# BTPlayer.net
KiCad netlist of a schematic drawn in EasyEDA
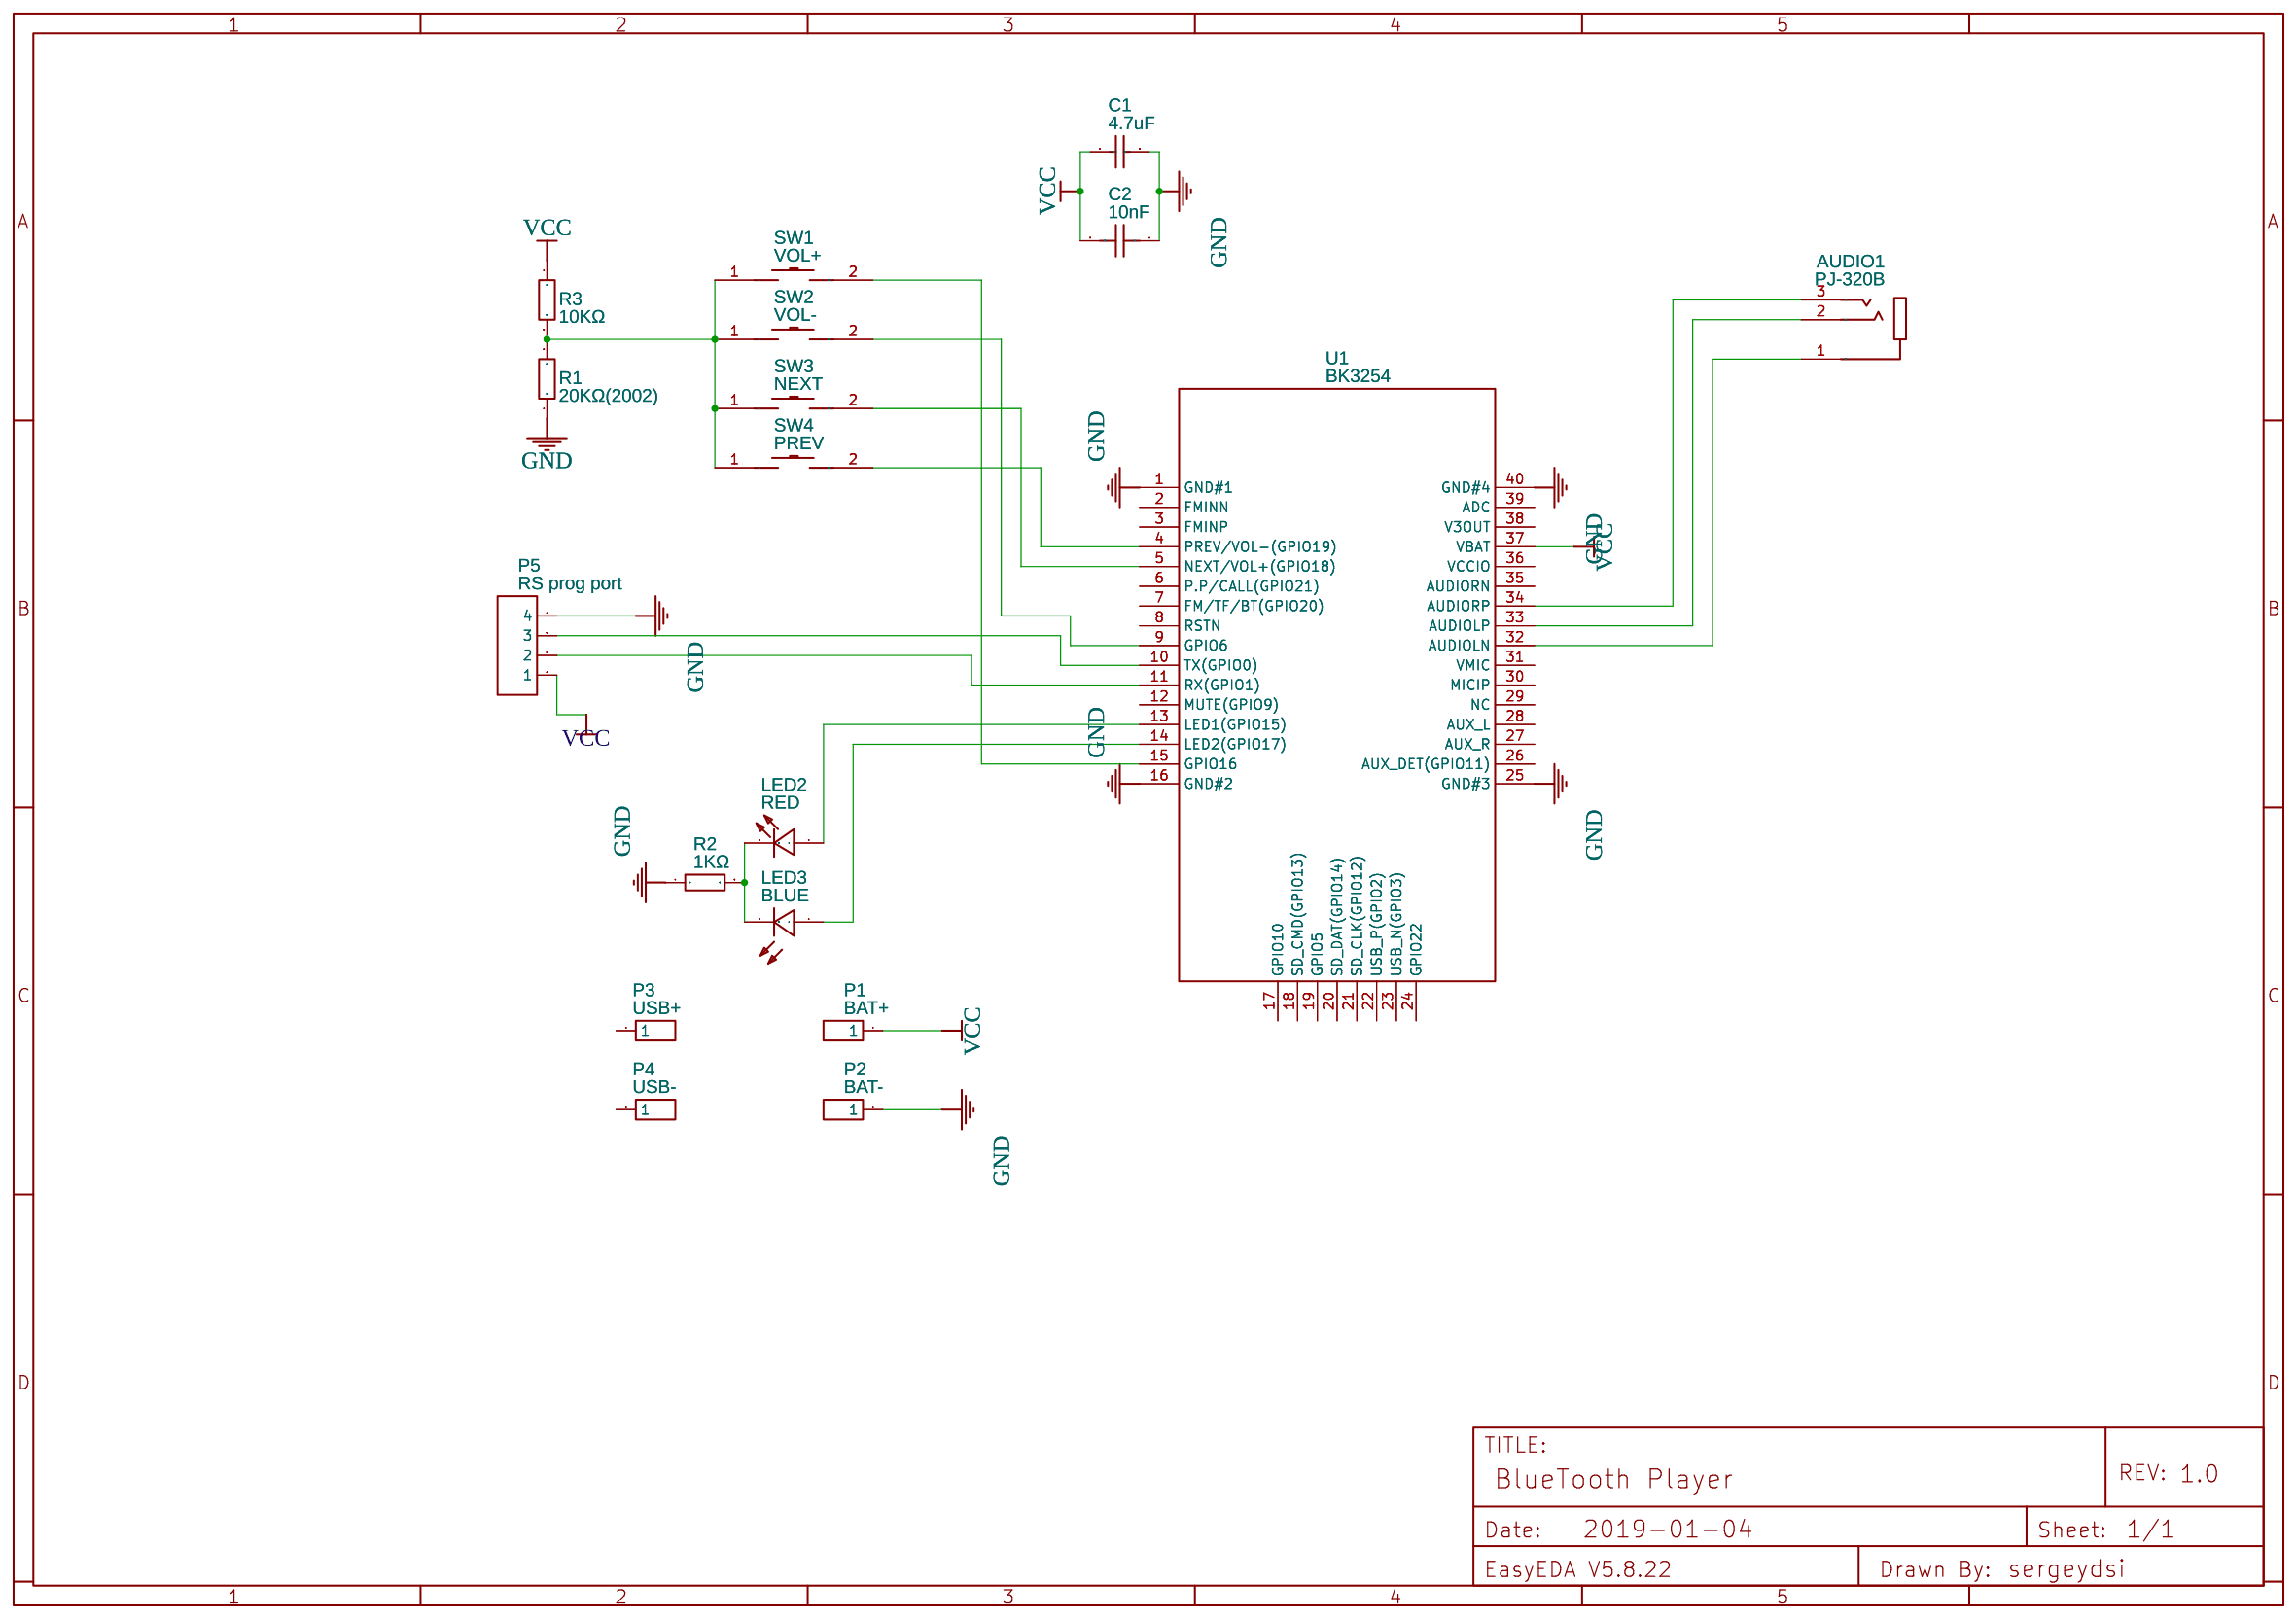
[diagram p0: schematic sheet]

(export (version "E")
  (design (tool "Eeschema 10.0.6"))
  (components
    (comp (ref "AUDIO1")
      (value "PJ-320B")
      (fields (field (name "BOM_Supplier Part") "C18594"))
      (libsource (lib "") (part "Unknown_935_165"))
    )
    (comp (ref "C1")
      (value "4.7uF")
      (fields
        (field (name "BOM_Manufacturer Part") "1206F475M500NT")
        (field (name "BOM_Supplier Part") "C46818")
      )
      (libsource (lib "") (part "1206F475M500NT"))
    )
    (comp (ref "C2")
      (value "10nF")
      (fields
        (field (name "BOM_Manufacturer Part") "1206B103K500")
        (field (name "BOM_Supplier Part") "C152840")
      )
      (libsource (lib "") (part "1206B103K500"))
    )
    (comp (ref "LED2")
      (value "RED")
      (fields
        (field (name "BOM_Manufacturer Part") "27-21/R6C-AP1Q2B/3C")
        (field (name "BOM_Supplier Part") "C183327")
      )
      (libsource (lib "") (part "Unknown_390_420"))
    )
    (comp (ref "LED3")
      (value "BLUE")
      (fields
        (field (name "BOM_Manufacturer Part") "27-21/BHC-AN1P2/3C")
        (field (name "BOM_Supplier Part") "C131261")
      )
      (libsource (lib "") (part "Unknown_390_460"))
    )
    (comp (ref "P1")
      (value "BAT+")
      (fields
        (field (name "BOM_Manufacturer Part") "Header-Male-2.54_1x1")
        (field (name "BOM_Supplier Part") "C81276")
      )
      (libsource (lib "") (part "Unknown_425_515"))
    )
    (comp (ref "P2")
      (value "BAT-")
      (fields
        (field (name "BOM_Manufacturer Part") "Header-Male-2.54_1x1")
        (field (name "BOM_Supplier Part") "C81276")
      )
      (libsource (lib "") (part "Unknown_425_555"))
    )
    (comp (ref "P3")
      (value "USB+")
      (fields
        (field (name "BOM_Manufacturer Part") "Header-Male-2.54_1x1")
        (field (name "BOM_Supplier Part") "C81276")
      )
      (libsource (lib "") (part "Unknown_320_515"))
    )
    (comp (ref "P4")
      (value "USB-")
      (fields
        (field (name "BOM_Manufacturer Part") "Header-Male-2.54_1x1")
        (field (name "BOM_Supplier Part") "C81276")
      )
      (libsource (lib "") (part "Unknown_320_555"))
    )
    (comp (ref "P5")
      (value "RS prog port")
      (fields
        (field (name "BOM_Manufacturer Part") "Header-Female-2.54_1x4")
        (field (name "BOM_Supplier Part") "C124413")
      )
      (libsource (lib "") (part "Unknown_260_320"))
    )
    (comp (ref "R1")
      (value "20KΩ(2002)")
      (fields
        (field (name "BOM_Manufacturer Part") "RTT032002FTP")
        (field (name "BOM_Supplier Part") "C103391")
      )
      (libsource (lib "") (part "RTT032002FTP"))
    )
    (comp (ref "R2")
      (value "1KΩ")
      (fields
        (field (name "BOM_Manufacturer Part") "0805W8F1001T5E")
        (field (name "BOM_Supplier Part") "C17513")
      )
      (libsource (lib "") (part "0805W8F1001T5E"))
    )
    (comp (ref "R3")
      (value "10KΩ")
      (fields
        (field (name "BOM_Manufacturer Part") "0603WAJ0103T5E")
        (field (name "BOM_Supplier Part") "C15401")
      )
      (libsource (lib "") (part "0603WAJ0103T5E"))
    )
    (comp (ref "SW1")
      (value "VOL+")
      (fields
        (field (name "BOM_Manufacturer Part") "K2-1112SA-A4SW-01")
        (field (name "BOM_Supplier Part") "C128949")
      )
      (libsource (lib "") (part "Unknown_395_130"))
    )
    (comp (ref "SW2")
      (value "VOL-")
      (fields
        (field (name "BOM_Manufacturer Part") "K2-1112SA-A4SW-01")
        (field (name "BOM_Supplier Part") "C128949")
      )
      (libsource (lib "") (part "Unknown_395_160"))
    )
    (comp (ref "SW3")
      (value "NEXT")
      (fields
        (field (name "BOM_Manufacturer Part") "K2-1112SA-A4SW-01")
        (field (name "BOM_Supplier Part") "C128949")
      )
      (libsource (lib "") (part "Unknown_395_195"))
    )
    (comp (ref "SW4")
      (value "PREV")
      (fields
        (field (name "BOM_Manufacturer Part") "K2-1112SA-A4SW-01")
        (field (name "BOM_Supplier Part") "C128949")
      )
      (libsource (lib "") (part "Unknown_395_225"))
    )
    (comp (ref "U1") (value "BK3254") (libsource (lib "") (part "Unknown_670_390")))
  )
  (nets
    (net (code "1") (name "GND") (class "Default")
      (node (ref "C1") (pin "2") (pinfunction "2_2") (pintype "input"))
      (node (ref "C2") (pin "1") (pinfunction "1_1") (pintype "unspecified"))
      (node (ref "P2") (pin "1") (pinfunction "1_1") (pintype "input"))
      (node (ref "P5") (pin "4") (pinfunction "4_4") (pintype "input"))
      (node (ref "R1") (pin "1") (pinfunction "1_1") (pintype "input"))
      (node (ref "R2") (pin "1") (pinfunction "1_1") (pintype "input"))
      (node (ref "U1") (pin "1") (pinfunction "GND#1_1") (pintype "unspecified"))
      (node (ref "U1") (pin "16") (pinfunction "GND#2_16") (pintype "unspecified"))
      (node (ref "U1") (pin "25") (pinfunction "GND#3_25") (pintype "unspecified"))
      (node (ref "U1") (pin "40") (pinfunction "GND#4_40") (pintype "unspecified"))
    )
    (net (code "2") (name "Net-(LED2-A)") (class "Default")
      (node (ref "LED2") (pin "1") (pinfunction "A_1") (pintype "unspecified"))
      (node (ref "U1") (pin "13") (pinfunction "LED1(GPIO15)_13") (pintype "unspecified"))
    )
    (net (code "3") (name "Net-(LED2-C)") (class "Default")
      (node (ref "LED2") (pin "2") (pinfunction "C_2") (pintype "unspecified"))
      (node (ref "LED3") (pin "2") (pinfunction "C_2") (pintype "unspecified"))
      (node (ref "R2") (pin "2") (pinfunction "2_2") (pintype "input"))
    )
    (net (code "4") (name "Net-(LED3-A)") (class "Default")
      (node (ref "LED3") (pin "1") (pinfunction "A_1") (pintype "unspecified"))
      (node (ref "U1") (pin "14") (pinfunction "LED2(GPIO17)_14") (pintype "unspecified"))
    )
    (net (code "5") (name "Net-(R1-Pad2)") (class "Default")
      (node (ref "R1") (pin "2") (pinfunction "2_2") (pintype "input"))
      (node (ref "R3") (pin "2") (pinfunction "2_2") (pintype "input"))
      (node (ref "SW1") (pin "1") (pinfunction "1_1") (pintype "unspecified"))
      (node (ref "SW2") (pin "1") (pinfunction "1_1") (pintype "unspecified"))
      (node (ref "SW3") (pin "1") (pinfunction "1_1") (pintype "unspecified"))
      (node (ref "SW4") (pin "1") (pinfunction "1_1") (pintype "unspecified"))
    )
    (net (code "6") (name "Net-(U1-AUDIOLN)") (class "Default")
      (node (ref "AUDIO1") (pin "1") (pinfunction "1_1") (pintype "unspecified"))
      (node (ref "U1") (pin "32") (pinfunction "AUDIOLN_32") (pintype "unspecified"))
    )
    (net (code "7") (name "Net-(U1-AUDIOLP)") (class "Default")
      (node (ref "AUDIO1") (pin "2") (pinfunction "2_2") (pintype "unspecified"))
      (node (ref "U1") (pin "33") (pinfunction "AUDIOLP_33") (pintype "unspecified"))
    )
    (net (code "8") (name "Net-(U1-AUDIORP)") (class "Default")
      (node (ref "AUDIO1") (pin "3") (pinfunction "3_3") (pintype "unspecified"))
      (node (ref "U1") (pin "34") (pinfunction "AUDIORP_34") (pintype "unspecified"))
    )
    (net (code "9") (name "Net-(U1-GPIO6)") (class "Default")
      (node (ref "SW2") (pin "2") (pinfunction "2_2") (pintype "unspecified"))
      (node (ref "U1") (pin "9") (pinfunction "GPIO6_9") (pintype "unspecified"))
    )
    (net (code "10") (name "Net-(U1-GPIO16)") (class "Default")
      (node (ref "SW1") (pin "2") (pinfunction "2_2") (pintype "unspecified"))
      (node (ref "U1") (pin "15") (pinfunction "GPIO16_15") (pintype "unspecified"))
    )
    (net (code "11") (name "Net-(U1-NEXT{slash}VOL+(GPIO18))") (class "Default")
      (node (ref "SW3") (pin "2") (pinfunction "2_2") (pintype "unspecified"))
      (node (ref "U1") (pin "5") (pinfunction "NEXT/VOL+(GPIO18)_5") (pintype "unspecified"))
    )
    (net (code "12") (name "Net-(U1-PREV{slash}VOL-(GPIO19))") (class "Default")
      (node (ref "SW4") (pin "2") (pinfunction "2_2") (pintype "unspecified"))
      (node (ref "U1") (pin "4") (pinfunction "PREV/VOL-(GPIO19)_4") (pintype "unspecified"))
    )
    (net (code "13") (name "Net-(U1-RX(GPIO1))") (class "Default")
      (node (ref "P5") (pin "2") (pinfunction "2_2") (pintype "input"))
      (node (ref "U1") (pin "11") (pinfunction "RX(GPIO1)_11") (pintype "unspecified"))
    )
    (net (code "14") (name "Net-(U1-TX(GPIO0))") (class "Default")
      (node (ref "P5") (pin "3") (pinfunction "3_3") (pintype "input"))
      (node (ref "U1") (pin "10") (pinfunction "TX(GPIO0)_10") (pintype "unspecified"))
    )
    (net (code "15") (name "VCC") (class "Default")
      (node (ref "C1") (pin "1") (pinfunction "1_1") (pintype "input"))
      (node (ref "C2") (pin "2") (pinfunction "2_2") (pintype "unspecified"))
      (node (ref "P1") (pin "1") (pinfunction "1_1") (pintype "input"))
      (node (ref "P5") (pin "1") (pinfunction "1_1") (pintype "input"))
      (node (ref "R3") (pin "1") (pinfunction "1_1") (pintype "input"))
      (node (ref "U1") (pin "37") (pinfunction "VBAT_37") (pintype "unspecified"))
    )
    (net (code "16") (name "unconnected-(P3-Pad1)") (class "Default")
      (node (ref "P3") (pin "1") (pinfunction "1_1") (pintype "input"))
    )
    (net (code "17") (name "unconnected-(P4-Pad1)") (class "Default")
      (node (ref "P4") (pin "1") (pinfunction "1_1") (pintype "input"))
    )
    (net (code "18") (name "unconnected-(U1-ADC-Pad39)") (class "Default")
      (node (ref "U1") (pin "39") (pinfunction "ADC_39") (pintype "unspecified"))
    )
    (net (code "19") (name "unconnected-(U1-AUDIORN-Pad35)") (class "Default")
      (node (ref "U1") (pin "35") (pinfunction "AUDIORN_35") (pintype "unspecified"))
    )
    (net (code "20") (name "unconnected-(U1-AUX_DET(GPIO11)-Pad26)") (class "Default")
      (node (ref "U1") (pin "26") (pinfunction "AUX_DET(GPIO11)_26") (pintype "unspecified"))
    )
    (net (code "21") (name "unconnected-(U1-AUX_L-Pad28)") (class "Default")
      (node (ref "U1") (pin "28") (pinfunction "AUX_L_28") (pintype "unspecified"))
    )
    (net (code "22") (name "unconnected-(U1-AUX_R-Pad27)") (class "Default")
      (node (ref "U1") (pin "27") (pinfunction "AUX_R_27") (pintype "unspecified"))
    )
    (net (code "23") (name "unconnected-(U1-FMINN-Pad2)") (class "Default")
      (node (ref "U1") (pin "2") (pinfunction "FMINN_2") (pintype "unspecified"))
    )
    (net (code "24") (name "unconnected-(U1-FMINP-Pad3)") (class "Default")
      (node (ref "U1") (pin "3") (pinfunction "FMINP_3") (pintype "unspecified"))
    )
    (net (code "25") (name "unconnected-(U1-FM{slash}TF{slash}BT(GPIO20)-Pad7)") (class "Default")
      (node (ref "U1") (pin "7") (pinfunction "FM/TF/BT(GPIO20)_7") (pintype "unspecified"))
    )
    (net (code "26") (name "unconnected-(U1-GPIO5-Pad19)") (class "Default")
      (node (ref "U1") (pin "19") (pinfunction "GPIO5_19") (pintype "unspecified"))
    )
    (net (code "27") (name "unconnected-(U1-GPIO10-Pad17)") (class "Default")
      (node (ref "U1") (pin "17") (pinfunction "GPIO10_17") (pintype "unspecified"))
    )
    (net (code "28") (name "unconnected-(U1-GPIO22-Pad24)") (class "Default")
      (node (ref "U1") (pin "24") (pinfunction "GPIO22_24") (pintype "unspecified"))
    )
    (net (code "29") (name "unconnected-(U1-MICIP-Pad30)") (class "Default")
      (node (ref "U1") (pin "30") (pinfunction "MICIP_30") (pintype "unspecified"))
    )
    (net (code "30") (name "unconnected-(U1-MUTE(GPIO9)-Pad12)") (class "Default")
      (node (ref "U1") (pin "12") (pinfunction "MUTE(GPIO9)_12") (pintype "unspecified"))
    )
    (net (code "31") (name "unconnected-(U1-NC-Pad29)") (class "Default")
      (node (ref "U1") (pin "29") (pinfunction "NC_29") (pintype "unspecified"))
    )
    (net (code "32") (name "unconnected-(U1-P.P{slash}CALL(GPIO21)-Pad6)") (class "Default")
      (node (ref "U1") (pin "6") (pinfunction "P.P/CALL(GPIO21)_6") (pintype "unspecified"))
    )
    (net (code "33") (name "unconnected-(U1-RSTN-Pad8)") (class "Default")
      (node (ref "U1") (pin "8") (pinfunction "RSTN_8") (pintype "unspecified"))
    )
    (net (code "34") (name "unconnected-(U1-SD_CLK(GPIO12)-Pad21)") (class "Default")
      (node (ref "U1") (pin "21") (pinfunction "SD_CLK(GPIO12)_21") (pintype "unspecified"))
    )
    (net (code "35") (name "unconnected-(U1-SD_CMD(GPIO13)-Pad18)") (class "Default")
      (node (ref "U1") (pin "18") (pinfunction "SD_CMD(GPIO13)_18") (pintype "unspecified"))
    )
    (net (code "36") (name "unconnected-(U1-SD_DAT(GPIO14)-Pad20)") (class "Default")
      (node (ref "U1") (pin "20") (pinfunction "SD_DAT(GPIO14)_20") (pintype "unspecified"))
    )
    (net (code "37") (name "unconnected-(U1-USB_N(GPIO3)-Pad23)") (class "Default")
      (node (ref "U1") (pin "23") (pinfunction "USB_N(GPIO3)_23") (pintype "unspecified"))
    )
    (net (code "38") (name "unconnected-(U1-USB_P(GPIO2)-Pad22)") (class "Default")
      (node (ref "U1") (pin "22") (pinfunction "USB_P(GPIO2)_22") (pintype "unspecified"))
    )
    (net (code "39") (name "unconnected-(U1-V3OUT-Pad38)") (class "Default")
      (node (ref "U1") (pin "38") (pinfunction "V3OUT_38") (pintype "unspecified"))
    )
    (net (code "40") (name "unconnected-(U1-VCCIO-Pad36)") (class "Default")
      (node (ref "U1") (pin "36") (pinfunction "VCCIO_36") (pintype "unspecified"))
    )
    (net (code "41") (name "unconnected-(U1-VMIC-Pad31)") (class "Default")
      (node (ref "U1") (pin "31") (pinfunction "VMIC_31") (pintype "unspecified"))
    )
  )
)
